# Mega_Shield-v13-VertPlace7.net
KiCad netlist of a schematic drawn in EAGLE
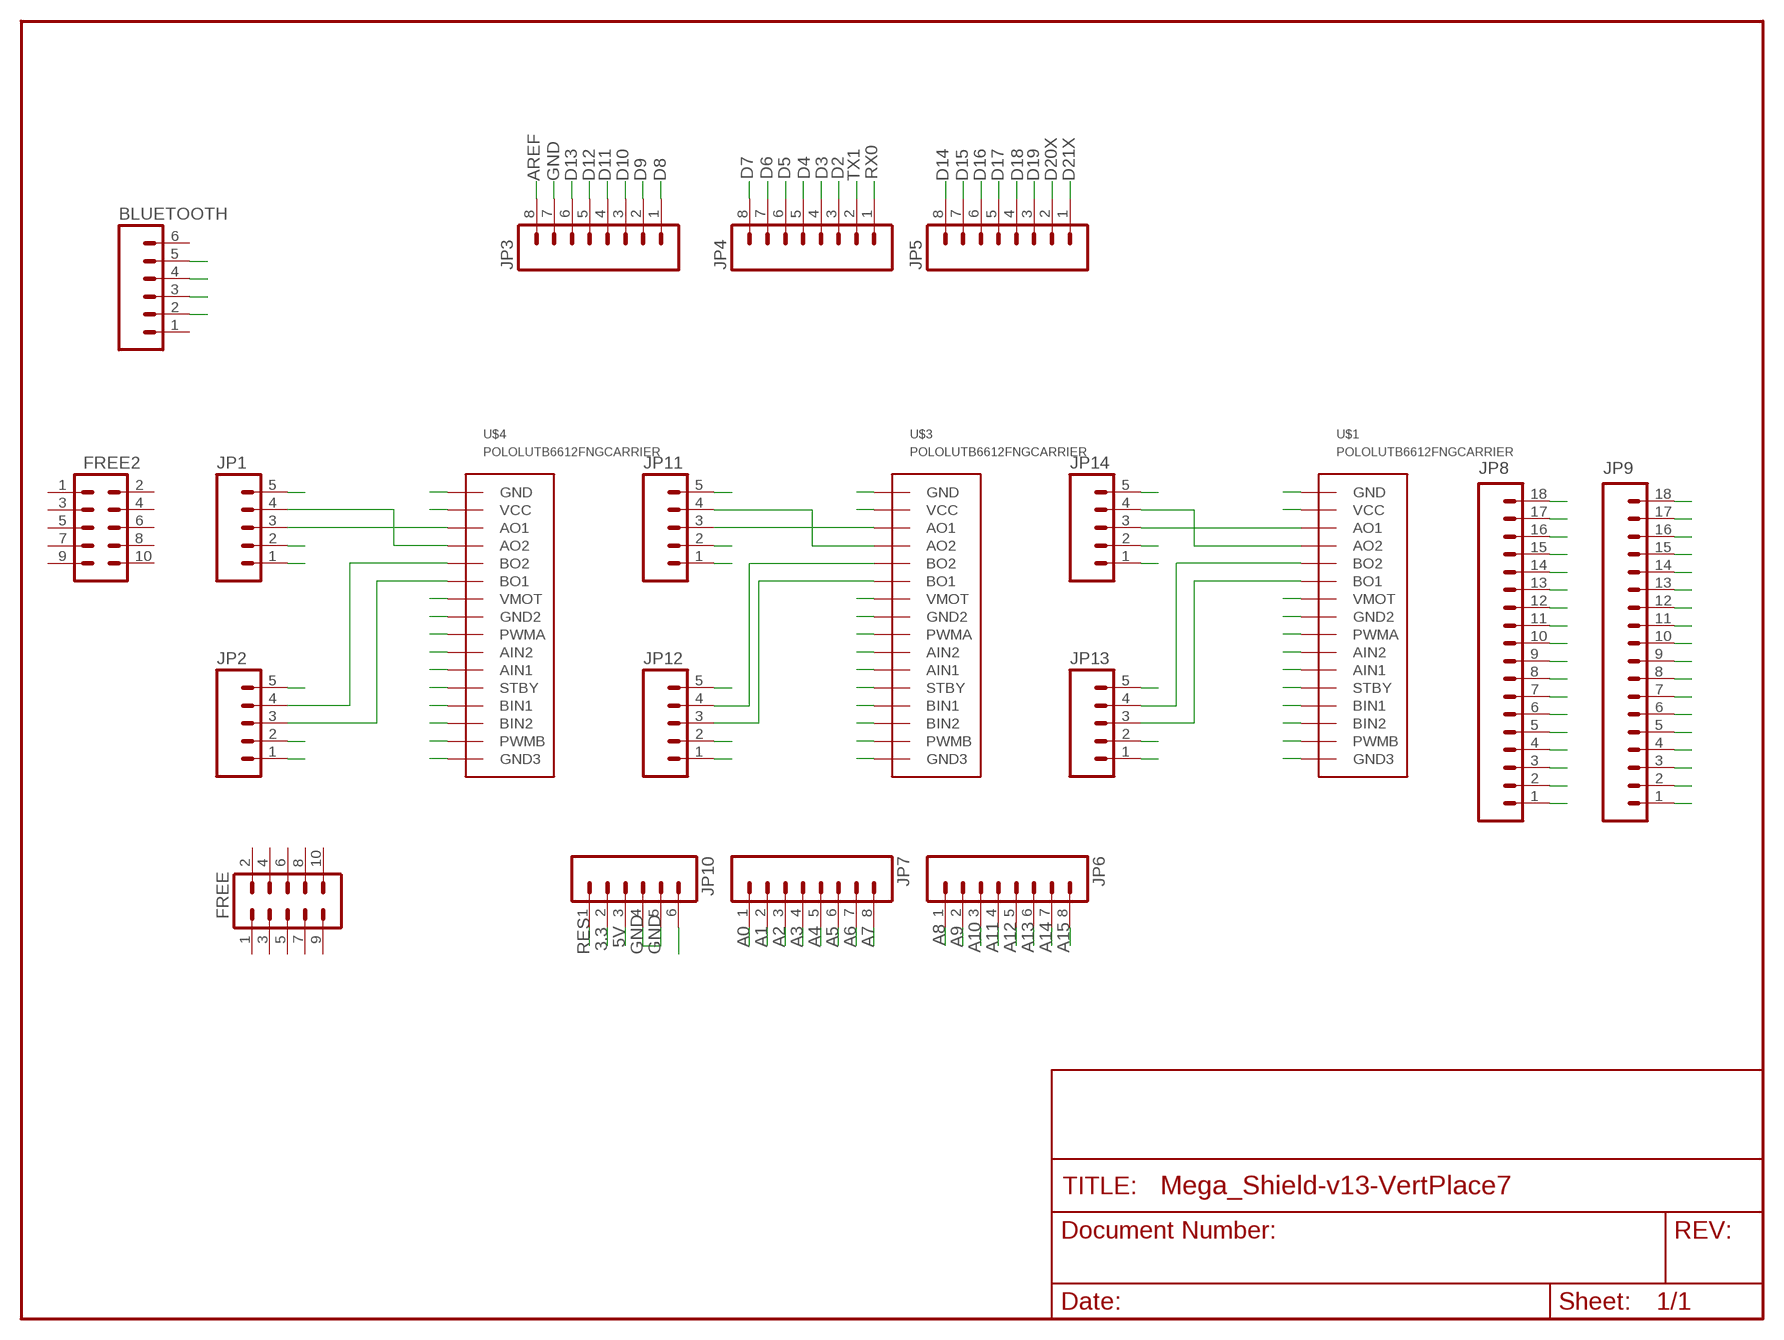
[diagram p0: schematic, sheet 1]

(export (version "E")
  (design (tool "Eeschema 10.0.6"))
  (components
    (comp (ref "BLUETOOTH")
      (value "M06FEMALE_LOCK")
      (footprint "eagle-import:1X06_FEMALE_LOCK.010")
      (libsource (lib "eagle-import") (part "SparkFun-Connectors_M06FEMALE_LOCK"))
    )
    (comp (ref "FREE")
      (value "M05X2NO_SILK")
      (footprint "eagle-import:2X5_NOSILK")
      (libsource (lib "eagle-import") (part "M05X2NO_SILK"))
    )
    (comp (ref "FREE2")
      (value "M05X2NO_SILK")
      (footprint "eagle-import:2X5_NOSILK")
      (libsource (lib "eagle-import") (part "M05X2NO_SILK"))
    )
    (comp (ref "JP1")
      (value "M05LOCK")
      (footprint "eagle-import:1X05_LOCK")
      (libsource (lib "eagle-import") (part "M05LOCK"))
    )
    (comp (ref "JP2")
      (value "M05LOCK")
      (footprint "eagle-import:1X05_LOCK")
      (libsource (lib "eagle-import") (part "M05LOCK"))
    )
    (comp (ref "JP3")
      (value "M08LOCK")
      (footprint "eagle-import:1X08_LOCK")
      (libsource (lib "eagle-import") (part "M08LOCK"))
    )
    (comp (ref "JP4")
      (value "M08LOCK")
      (footprint "eagle-import:1X08_LOCK")
      (libsource (lib "eagle-import") (part "M08LOCK"))
    )
    (comp (ref "JP5")
      (value "M08LOCK")
      (footprint "eagle-import:1X08_LOCK")
      (libsource (lib "eagle-import") (part "M08LOCK"))
    )
    (comp (ref "JP6")
      (value "M08LOCK")
      (footprint "eagle-import:1X08_LOCK")
      (libsource (lib "eagle-import") (part "M08LOCK"))
    )
    (comp (ref "JP7")
      (value "M08LOCK")
      (footprint "eagle-import:1X08_LOCK")
      (libsource (lib "eagle-import") (part "M08LOCK"))
    )
    (comp (ref "JP8")
      (value "M18_")
      (footprint "eagle-import:1X18")
      (libsource (lib "eagle-import") (part "M18_"))
    )
    (comp (ref "JP9")
      (value "M18_")
      (footprint "eagle-import:1X18")
      (libsource (lib "eagle-import") (part "M18_"))
    )
    (comp (ref "JP10")
      (value "M06LOCK")
      (footprint "eagle-import:1X06_LOCK")
      (libsource (lib "eagle-import") (part "M06LOCK"))
    )
    (comp (ref "JP11")
      (value "M05LOCK")
      (footprint "eagle-import:1X05_LOCK")
      (libsource (lib "eagle-import") (part "M05LOCK"))
    )
    (comp (ref "JP12")
      (value "M05LOCK")
      (footprint "eagle-import:1X05_LOCK")
      (libsource (lib "eagle-import") (part "M05LOCK"))
    )
    (comp (ref "JP13")
      (value "M05LOCK")
      (footprint "eagle-import:1X05_LOCK")
      (libsource (lib "eagle-import") (part "M05LOCK"))
    )
    (comp (ref "JP14")
      (value "M05LOCK")
      (footprint "eagle-import:1X05_LOCK")
      (libsource (lib "eagle-import") (part "M05LOCK"))
    )
    (comp (ref "U$1")
      (value "POLOLUTB6612FNGCARRIER")
      (footprint "eagle-import:THROUGHHOLECARRIER")
      (libsource (lib "eagle-import") (part "POLOLUTB6612FNGCARRIER"))
    )
    (comp (ref "U$3")
      (value "POLOLUTB6612FNGCARRIER")
      (footprint "eagle-import:THROUGHHOLECARRIER")
      (libsource (lib "eagle-import") (part "POLOLUTB6612FNGCARRIER"))
    )
    (comp (ref "U$4")
      (value "POLOLUTB6612FNGCARRIER")
      (footprint "eagle-import:THROUGHHOLECARRIER")
      (libsource (lib "eagle-import") (part "POLOLUTB6612FNGCARRIER"))
    )
  )
  (nets
    (net (code "1") (name "/3.3") (class "Default")
      (node (ref "JP10") (pin "2") (pinfunction "2_2") (pintype "passive"))
    )
    (net (code "2") (name "/5V") (class "Default")
      (node (ref "BLUETOOTH") (pin "5") (pinfunction "5_5") (pintype "passive"))
      (node (ref "JP1") (pin "5") (pinfunction "5_5") (pintype "passive"))
      (node (ref "JP10") (pin "3") (pinfunction "3_3") (pintype "passive"))
      (node (ref "JP11") (pin "5") (pinfunction "5_5") (pintype "passive"))
      (node (ref "JP12") (pin "5") (pinfunction "5_5") (pintype "passive"))
      (node (ref "JP13") (pin "5") (pinfunction "5_5") (pintype "passive"))
      (node (ref "JP14") (pin "5") (pinfunction "5_5") (pintype "passive"))
      (node (ref "JP2") (pin "5") (pinfunction "5_5") (pintype "passive"))
      (node (ref "JP8") (pin "18") (pinfunction "18_18") (pintype "passive"))
      (node (ref "JP9") (pin "18") (pinfunction "18_18") (pintype "passive"))
      (node (ref "U$1") (pin "12") (pinfunction "STBY_12") (pintype "passive"))
      (node (ref "U$1") (pin "2") (pinfunction "VCC_2") (pintype "passive"))
      (node (ref "U$3") (pin "12") (pinfunction "STBY_12") (pintype "passive"))
      (node (ref "U$3") (pin "2") (pinfunction "VCC_2") (pintype "passive"))
      (node (ref "U$4") (pin "12") (pinfunction "STBY_12") (pintype "passive"))
      (node (ref "U$4") (pin "2") (pinfunction "VCC_2") (pintype "passive"))
    )
    (net (code "3") (name "/A0") (class "Default")
      (node (ref "JP14") (pin "2") (pinfunction "2_2") (pintype "passive"))
      (node (ref "JP7") (pin "1") (pinfunction "1_1") (pintype "passive"))
    )
    (net (code "4") (name "/A1") (class "Default")
      (node (ref "JP13") (pin "2") (pinfunction "2_2") (pintype "passive"))
      (node (ref "JP7") (pin "2") (pinfunction "2_2") (pintype "passive"))
    )
    (net (code "5") (name "/A2") (class "Default")
      (node (ref "JP11") (pin "2") (pinfunction "2_2") (pintype "passive"))
      (node (ref "JP7") (pin "3") (pinfunction "3_3") (pintype "passive"))
    )
    (net (code "6") (name "/A3") (class "Default")
      (node (ref "JP12") (pin "2") (pinfunction "2_2") (pintype "passive"))
      (node (ref "JP7") (pin "4") (pinfunction "4_4") (pintype "passive"))
    )
    (net (code "7") (name "/A4") (class "Default")
      (node (ref "JP1") (pin "2") (pinfunction "2_2") (pintype "passive"))
      (node (ref "JP7") (pin "5") (pinfunction "5_5") (pintype "passive"))
    )
    (net (code "8") (name "/A5") (class "Default")
      (node (ref "JP2") (pin "2") (pinfunction "2_2") (pintype "passive"))
      (node (ref "JP7") (pin "6") (pinfunction "6_6") (pintype "passive"))
    )
    (net (code "9") (name "/A6") (class "Default")
      (node (ref "JP7") (pin "7") (pinfunction "7_7") (pintype "passive"))
    )
    (net (code "10") (name "/A7") (class "Default")
      (node (ref "JP7") (pin "8") (pinfunction "8_8") (pintype "passive"))
    )
    (net (code "11") (name "/A8") (class "Default")
      (node (ref "JP6") (pin "1") (pinfunction "1_1") (pintype "passive"))
    )
    (net (code "12") (name "/A9") (class "Default")
      (node (ref "JP6") (pin "2") (pinfunction "2_2") (pintype "passive"))
    )
    (net (code "13") (name "/A10") (class "Default")
      (node (ref "JP6") (pin "3") (pinfunction "3_3") (pintype "passive"))
    )
    (net (code "14") (name "/A11") (class "Default")
      (node (ref "JP6") (pin "4") (pinfunction "4_4") (pintype "passive"))
    )
    (net (code "15") (name "/A12") (class "Default")
      (node (ref "JP6") (pin "5") (pinfunction "5_5") (pintype "passive"))
    )
    (net (code "16") (name "/A13") (class "Default")
      (node (ref "JP6") (pin "6") (pinfunction "6_6") (pintype "passive"))
    )
    (net (code "17") (name "/A14") (class "Default")
      (node (ref "JP6") (pin "7") (pinfunction "7_7") (pintype "passive"))
    )
    (net (code "18") (name "/A15") (class "Default")
      (node (ref "JP6") (pin "8") (pinfunction "8_8") (pintype "passive"))
    )
    (net (code "19") (name "/AREF") (class "Default")
      (node (ref "JP3") (pin "8") (pinfunction "8_8") (pintype "passive"))
    )
    (net (code "20") (name "/D2") (class "Default")
      (node (ref "JP4") (pin "3") (pinfunction "3_3") (pintype "passive"))
      (node (ref "U$1") (pin "9") (pinfunction "PWMA_9") (pintype "passive"))
    )
    (net (code "21") (name "/D3") (class "Default")
      (node (ref "JP4") (pin "4") (pinfunction "4_4") (pintype "passive"))
      (node (ref "U$1") (pin "15") (pinfunction "PWMB_15") (pintype "passive"))
    )
    (net (code "22") (name "/D4") (class "Default")
      (node (ref "JP4") (pin "5") (pinfunction "5_5") (pintype "passive"))
      (node (ref "U$3") (pin "9") (pinfunction "PWMA_9") (pintype "passive"))
    )
    (net (code "23") (name "/D5") (class "Default")
      (node (ref "JP4") (pin "6") (pinfunction "6_6") (pintype "passive"))
      (node (ref "U$3") (pin "15") (pinfunction "PWMB_15") (pintype "passive"))
    )
    (net (code "24") (name "/D6") (class "Default")
      (node (ref "JP4") (pin "7") (pinfunction "7_7") (pintype "passive"))
      (node (ref "U$4") (pin "9") (pinfunction "PWMA_9") (pintype "passive"))
    )
    (net (code "25") (name "/D7") (class "Default")
      (node (ref "JP4") (pin "8") (pinfunction "8_8") (pintype "passive"))
      (node (ref "U$4") (pin "15") (pinfunction "PWMB_15") (pintype "passive"))
    )
    (net (code "26") (name "/D8") (class "Default")
      (node (ref "JP3") (pin "1") (pinfunction "1_1") (pintype "passive"))
    )
    (net (code "27") (name "/D9") (class "Default")
      (node (ref "JP3") (pin "2") (pinfunction "2_2") (pintype "passive"))
    )
    (net (code "28") (name "/D10") (class "Default")
      (node (ref "JP3") (pin "3") (pinfunction "3_3") (pintype "passive"))
    )
    (net (code "29") (name "/D11") (class "Default")
      (node (ref "JP3") (pin "4") (pinfunction "4_4") (pintype "passive"))
    )
    (net (code "30") (name "/D12") (class "Default")
      (node (ref "BLUETOOTH") (pin "2") (pinfunction "2_2") (pintype "passive"))
      (node (ref "JP3") (pin "5") (pinfunction "5_5") (pintype "passive"))
    )
    (net (code "31") (name "/D13") (class "Default")
      (node (ref "BLUETOOTH") (pin "3") (pinfunction "3_3") (pintype "passive"))
      (node (ref "JP3") (pin "6") (pinfunction "6_6") (pintype "passive"))
    )
    (net (code "32") (name "/D14") (class "Default")
      (node (ref "JP5") (pin "8") (pinfunction "8_8") (pintype "passive"))
    )
    (net (code "33") (name "/D15") (class "Default")
      (node (ref "JP5") (pin "7") (pinfunction "7_7") (pintype "passive"))
    )
    (net (code "34") (name "/D16") (class "Default")
      (node (ref "JP5") (pin "6") (pinfunction "6_6") (pintype "passive"))
    )
    (net (code "35") (name "/D17") (class "Default")
      (node (ref "JP5") (pin "5") (pinfunction "5_5") (pintype "passive"))
    )
    (net (code "36") (name "/D18") (class "Default")
      (node (ref "JP5") (pin "4") (pinfunction "4_4") (pintype "passive"))
    )
    (net (code "37") (name "/D19") (class "Default")
      (node (ref "JP5") (pin "3") (pinfunction "3_3") (pintype "passive"))
    )
    (net (code "38") (name "/D20X") (class "Default")
      (node (ref "JP5") (pin "2") (pinfunction "2_2") (pintype "passive"))
    )
    (net (code "39") (name "/D21X") (class "Default")
      (node (ref "JP5") (pin "1") (pinfunction "1_1") (pintype "passive"))
    )
    (net (code "40") (name "/D42") (class "Default")
      (node (ref "JP8") (pin "7") (pinfunction "7_7") (pintype "passive"))
      (node (ref "U$4") (pin "14") (pinfunction "BIN2_14") (pintype "passive"))
    )
    (net (code "41") (name "/D43") (class "Default")
      (node (ref "JP9") (pin "7") (pinfunction "7_7") (pintype "passive"))
      (node (ref "U$4") (pin "13") (pinfunction "BIN1_13") (pintype "passive"))
    )
    (net (code "42") (name "/D44") (class "Default")
      (node (ref "JP8") (pin "6") (pinfunction "6_6") (pintype "passive"))
      (node (ref "U$4") (pin "10") (pinfunction "AIN2_10") (pintype "passive"))
    )
    (net (code "43") (name "/D45") (class "Default")
      (node (ref "JP9") (pin "6") (pinfunction "6_6") (pintype "passive"))
      (node (ref "U$4") (pin "11") (pinfunction "AIN1_11") (pintype "passive"))
    )
    (net (code "44") (name "/D46") (class "Default")
      (node (ref "JP8") (pin "5") (pinfunction "5_5") (pintype "passive"))
      (node (ref "U$3") (pin "14") (pinfunction "BIN2_14") (pintype "passive"))
    )
    (net (code "45") (name "/D47") (class "Default")
      (node (ref "JP9") (pin "5") (pinfunction "5_5") (pintype "passive"))
      (node (ref "U$3") (pin "13") (pinfunction "BIN1_13") (pintype "passive"))
    )
    (net (code "46") (name "/D48") (class "Default")
      (node (ref "JP8") (pin "4") (pinfunction "4_4") (pintype "passive"))
      (node (ref "U$3") (pin "10") (pinfunction "AIN2_10") (pintype "passive"))
    )
    (net (code "47") (name "/D49") (class "Default")
      (node (ref "JP9") (pin "4") (pinfunction "4_4") (pintype "passive"))
      (node (ref "U$3") (pin "11") (pinfunction "AIN1_11") (pintype "passive"))
    )
    (net (code "48") (name "/D50") (class "Default")
      (node (ref "JP8") (pin "3") (pinfunction "3_3") (pintype "passive"))
      (node (ref "U$1") (pin "14") (pinfunction "BIN2_14") (pintype "passive"))
    )
    (net (code "49") (name "/D51") (class "Default")
      (node (ref "JP9") (pin "3") (pinfunction "3_3") (pintype "passive"))
      (node (ref "U$1") (pin "13") (pinfunction "BIN1_13") (pintype "passive"))
    )
    (net (code "50") (name "/D52") (class "Default")
      (node (ref "JP8") (pin "2") (pinfunction "2_2") (pintype "passive"))
      (node (ref "U$1") (pin "10") (pinfunction "AIN2_10") (pintype "passive"))
    )
    (net (code "51") (name "/D53") (class "Default")
      (node (ref "JP9") (pin "2") (pinfunction "2_2") (pintype "passive"))
      (node (ref "U$1") (pin "11") (pinfunction "AIN1_11") (pintype "passive"))
    )
    (net (code "52") (name "/GND") (class "Default")
      (node (ref "BLUETOOTH") (pin "4") (pinfunction "4_4") (pintype "passive"))
      (node (ref "JP1") (pin "1") (pinfunction "1_1") (pintype "passive"))
      (node (ref "JP10") (pin "4") (pinfunction "4_4") (pintype "passive"))
      (node (ref "JP10") (pin "5") (pinfunction "5_5") (pintype "passive"))
      (node (ref "JP11") (pin "1") (pinfunction "1_1") (pintype "passive"))
      (node (ref "JP12") (pin "1") (pinfunction "1_1") (pintype "passive"))
      (node (ref "JP13") (pin "1") (pinfunction "1_1") (pintype "passive"))
      (node (ref "JP14") (pin "1") (pinfunction "1_1") (pintype "passive"))
      (node (ref "JP2") (pin "1") (pinfunction "1_1") (pintype "passive"))
      (node (ref "JP3") (pin "7") (pinfunction "7_7") (pintype "passive"))
      (node (ref "JP8") (pin "1") (pinfunction "1_1") (pintype "passive"))
      (node (ref "JP9") (pin "1") (pinfunction "1_1") (pintype "passive"))
      (node (ref "U$1") (pin "1") (pinfunction "GND_1") (pintype "passive"))
      (node (ref "U$1") (pin "16") (pinfunction "GND3_16") (pintype "passive"))
      (node (ref "U$1") (pin "8") (pinfunction "GND2_8") (pintype "passive"))
      (node (ref "U$3") (pin "1") (pinfunction "GND_1") (pintype "passive"))
      (node (ref "U$3") (pin "16") (pinfunction "GND3_16") (pintype "passive"))
      (node (ref "U$3") (pin "8") (pinfunction "GND2_8") (pintype "passive"))
      (node (ref "U$4") (pin "1") (pinfunction "GND_1") (pintype "passive"))
      (node (ref "U$4") (pin "16") (pinfunction "GND3_16") (pintype "passive"))
      (node (ref "U$4") (pin "8") (pinfunction "GND2_8") (pintype "passive"))
    )
    (net (code "53") (name "/RES") (class "Default")
      (node (ref "JP10") (pin "1") (pinfunction "1_1") (pintype "passive"))
    )
    (net (code "54") (name "/RX0") (class "Default")
      (node (ref "JP4") (pin "1") (pinfunction "1_1") (pintype "passive"))
    )
    (net (code "55") (name "/TX1") (class "Default")
      (node (ref "JP4") (pin "2") (pinfunction "2_2") (pintype "passive"))
    )
    (net (code "56") (name "/VIN") (class "Default")
      (node (ref "JP10") (pin "6") (pinfunction "6_6") (pintype "passive"))
      (node (ref "U$1") (pin "7") (pinfunction "VMOT_7") (pintype "passive"))
      (node (ref "U$3") (pin "7") (pinfunction "VMOT_7") (pintype "passive"))
      (node (ref "U$4") (pin "7") (pinfunction "VMOT_7") (pintype "passive"))
    )
    (net (code "57") (name "Net-(U$1-AO1)") (class "Default")
      (node (ref "JP14") (pin "3") (pinfunction "3_3") (pintype "passive"))
      (node (ref "U$1") (pin "3") (pinfunction "AO1_3") (pintype "passive"))
    )
    (net (code "58") (name "Net-(U$1-AO2)") (class "Default")
      (node (ref "JP14") (pin "4") (pinfunction "4_4") (pintype "passive"))
      (node (ref "U$1") (pin "4") (pinfunction "AO2_4") (pintype "passive"))
    )
    (net (code "59") (name "Net-(U$1-BO1)") (class "Default")
      (node (ref "JP13") (pin "3") (pinfunction "3_3") (pintype "passive"))
      (node (ref "U$1") (pin "6") (pinfunction "BO1_6") (pintype "passive"))
    )
    (net (code "60") (name "Net-(U$1-BO2)") (class "Default")
      (node (ref "JP13") (pin "4") (pinfunction "4_4") (pintype "passive"))
      (node (ref "U$1") (pin "5") (pinfunction "BO2_5") (pintype "passive"))
    )
    (net (code "61") (name "Net-(U$3-AO1)") (class "Default")
      (node (ref "JP11") (pin "3") (pinfunction "3_3") (pintype "passive"))
      (node (ref "U$3") (pin "3") (pinfunction "AO1_3") (pintype "passive"))
    )
    (net (code "62") (name "Net-(U$3-AO2)") (class "Default")
      (node (ref "JP11") (pin "4") (pinfunction "4_4") (pintype "passive"))
      (node (ref "U$3") (pin "4") (pinfunction "AO2_4") (pintype "passive"))
    )
    (net (code "63") (name "Net-(U$3-BO1)") (class "Default")
      (node (ref "JP12") (pin "3") (pinfunction "3_3") (pintype "passive"))
      (node (ref "U$3") (pin "6") (pinfunction "BO1_6") (pintype "passive"))
    )
    (net (code "64") (name "Net-(U$3-BO2)") (class "Default")
      (node (ref "JP12") (pin "4") (pinfunction "4_4") (pintype "passive"))
      (node (ref "U$3") (pin "5") (pinfunction "BO2_5") (pintype "passive"))
    )
    (net (code "65") (name "Net-(U$4-AO1)") (class "Default")
      (node (ref "JP1") (pin "3") (pinfunction "3_3") (pintype "passive"))
      (node (ref "U$4") (pin "3") (pinfunction "AO1_3") (pintype "passive"))
    )
    (net (code "66") (name "Net-(U$4-AO2)") (class "Default")
      (node (ref "JP1") (pin "4") (pinfunction "4_4") (pintype "passive"))
      (node (ref "U$4") (pin "4") (pinfunction "AO2_4") (pintype "passive"))
    )
    (net (code "67") (name "Net-(U$4-BO1)") (class "Default")
      (node (ref "JP2") (pin "3") (pinfunction "3_3") (pintype "passive"))
      (node (ref "U$4") (pin "6") (pinfunction "BO1_6") (pintype "passive"))
    )
    (net (code "68") (name "Net-(U$4-BO2)") (class "Default")
      (node (ref "JP2") (pin "4") (pinfunction "4_4") (pintype "passive"))
      (node (ref "U$4") (pin "5") (pinfunction "BO2_5") (pintype "passive"))
    )
    (net (code "69") (name "unconnected-(BLUETOOTH-Pad1)") (class "Default")
      (node (ref "BLUETOOTH") (pin "1") (pinfunction "1_1") (pintype "passive"))
    )
    (net (code "70") (name "unconnected-(BLUETOOTH-Pad6)") (class "Default")
      (node (ref "BLUETOOTH") (pin "6") (pinfunction "6_6") (pintype "passive"))
    )
    (net (code "71") (name "unconnected-(FREE-Pad1)") (class "Default")
      (node (ref "FREE") (pin "1") (pinfunction "1_1") (pintype "passive"))
    )
    (net (code "72") (name "unconnected-(FREE-Pad2)") (class "Default")
      (node (ref "FREE") (pin "2") (pinfunction "2_2") (pintype "passive"))
    )
    (net (code "73") (name "unconnected-(FREE-Pad3)") (class "Default")
      (node (ref "FREE") (pin "3") (pinfunction "3_3") (pintype "passive"))
    )
    (net (code "74") (name "unconnected-(FREE-Pad4)") (class "Default")
      (node (ref "FREE") (pin "4") (pinfunction "4_4") (pintype "passive"))
    )
    (net (code "75") (name "unconnected-(FREE-Pad5)") (class "Default")
      (node (ref "FREE") (pin "5") (pinfunction "5_5") (pintype "passive"))
    )
    (net (code "76") (name "unconnected-(FREE-Pad6)") (class "Default")
      (node (ref "FREE") (pin "6") (pinfunction "6_6") (pintype "passive"))
    )
    (net (code "77") (name "unconnected-(FREE-Pad7)") (class "Default")
      (node (ref "FREE") (pin "7") (pinfunction "7_7") (pintype "passive"))
    )
    (net (code "78") (name "unconnected-(FREE-Pad8)") (class "Default")
      (node (ref "FREE") (pin "8") (pinfunction "8_8") (pintype "passive"))
    )
    (net (code "79") (name "unconnected-(FREE-Pad9)") (class "Default")
      (node (ref "FREE") (pin "9") (pinfunction "9_9") (pintype "passive"))
    )
    (net (code "80") (name "unconnected-(FREE-Pad10)") (class "Default")
      (node (ref "FREE") (pin "10") (pinfunction "10_10") (pintype "passive"))
    )
    (net (code "81") (name "unconnected-(FREE2-Pad1)") (class "Default")
      (node (ref "FREE2") (pin "1") (pinfunction "1_1") (pintype "passive"))
    )
    (net (code "82") (name "unconnected-(FREE2-Pad2)") (class "Default")
      (node (ref "FREE2") (pin "2") (pinfunction "2_2") (pintype "passive"))
    )
    (net (code "83") (name "unconnected-(FREE2-Pad3)") (class "Default")
      (node (ref "FREE2") (pin "3") (pinfunction "3_3") (pintype "passive"))
    )
    (net (code "84") (name "unconnected-(FREE2-Pad4)") (class "Default")
      (node (ref "FREE2") (pin "4") (pinfunction "4_4") (pintype "passive"))
    )
    (net (code "85") (name "unconnected-(FREE2-Pad5)") (class "Default")
      (node (ref "FREE2") (pin "5") (pinfunction "5_5") (pintype "passive"))
    )
    (net (code "86") (name "unconnected-(FREE2-Pad6)") (class "Default")
      (node (ref "FREE2") (pin "6") (pinfunction "6_6") (pintype "passive"))
    )
    (net (code "87") (name "unconnected-(FREE2-Pad7)") (class "Default")
      (node (ref "FREE2") (pin "7") (pinfunction "7_7") (pintype "passive"))
    )
    (net (code "88") (name "unconnected-(FREE2-Pad8)") (class "Default")
      (node (ref "FREE2") (pin "8") (pinfunction "8_8") (pintype "passive"))
    )
    (net (code "89") (name "unconnected-(FREE2-Pad9)") (class "Default")
      (node (ref "FREE2") (pin "9") (pinfunction "9_9") (pintype "passive"))
    )
    (net (code "90") (name "unconnected-(FREE2-Pad10)") (class "Default")
      (node (ref "FREE2") (pin "10") (pinfunction "10_10") (pintype "passive"))
    )
    (net (code "91") (name "unconnected-(JP8-Pad8)") (class "Default")
      (node (ref "JP8") (pin "8") (pinfunction "8_8") (pintype "passive"))
    )
    (net (code "92") (name "unconnected-(JP8-Pad9)") (class "Default")
      (node (ref "JP8") (pin "9") (pinfunction "9_9") (pintype "passive"))
    )
    (net (code "93") (name "unconnected-(JP8-Pad10)") (class "Default")
      (node (ref "JP8") (pin "10") (pinfunction "10_10") (pintype "passive"))
    )
    (net (code "94") (name "unconnected-(JP8-Pad11)") (class "Default")
      (node (ref "JP8") (pin "11") (pinfunction "11_11") (pintype "passive"))
    )
    (net (code "95") (name "unconnected-(JP8-Pad12)") (class "Default")
      (node (ref "JP8") (pin "12") (pinfunction "12_12") (pintype "passive"))
    )
    (net (code "96") (name "unconnected-(JP8-Pad13)") (class "Default")
      (node (ref "JP8") (pin "13") (pinfunction "13_13") (pintype "passive"))
    )
    (net (code "97") (name "unconnected-(JP8-Pad14)") (class "Default")
      (node (ref "JP8") (pin "14") (pinfunction "14_14") (pintype "passive"))
    )
    (net (code "98") (name "unconnected-(JP8-Pad15)") (class "Default")
      (node (ref "JP8") (pin "15") (pinfunction "15_15") (pintype "passive"))
    )
    (net (code "99") (name "unconnected-(JP8-Pad16)") (class "Default")
      (node (ref "JP8") (pin "16") (pinfunction "16_16") (pintype "passive"))
    )
    (net (code "100") (name "unconnected-(JP8-Pad17)") (class "Default")
      (node (ref "JP8") (pin "17") (pinfunction "17_17") (pintype "passive"))
    )
    (net (code "101") (name "unconnected-(JP9-Pad8)") (class "Default")
      (node (ref "JP9") (pin "8") (pinfunction "8_8") (pintype "passive"))
    )
    (net (code "102") (name "unconnected-(JP9-Pad9)") (class "Default")
      (node (ref "JP9") (pin "9") (pinfunction "9_9") (pintype "passive"))
    )
    (net (code "103") (name "unconnected-(JP9-Pad10)") (class "Default")
      (node (ref "JP9") (pin "10") (pinfunction "10_10") (pintype "passive"))
    )
    (net (code "104") (name "unconnected-(JP9-Pad11)") (class "Default")
      (node (ref "JP9") (pin "11") (pinfunction "11_11") (pintype "passive"))
    )
    (net (code "105") (name "unconnected-(JP9-Pad12)") (class "Default")
      (node (ref "JP9") (pin "12") (pinfunction "12_12") (pintype "passive"))
    )
    (net (code "106") (name "unconnected-(JP9-Pad13)") (class "Default")
      (node (ref "JP9") (pin "13") (pinfunction "13_13") (pintype "passive"))
    )
    (net (code "107") (name "unconnected-(JP9-Pad14)") (class "Default")
      (node (ref "JP9") (pin "14") (pinfunction "14_14") (pintype "passive"))
    )
    (net (code "108") (name "unconnected-(JP9-Pad15)") (class "Default")
      (node (ref "JP9") (pin "15") (pinfunction "15_15") (pintype "passive"))
    )
    (net (code "109") (name "unconnected-(JP9-Pad16)") (class "Default")
      (node (ref "JP9") (pin "16") (pinfunction "16_16") (pintype "passive"))
    )
    (net (code "110") (name "unconnected-(JP9-Pad17)") (class "Default")
      (node (ref "JP9") (pin "17") (pinfunction "17_17") (pintype "passive"))
    )
  )
)
